# HDMI_OUTPUT_AD9889.net
KiCad netlist of a schematic drawn in Altium Designer
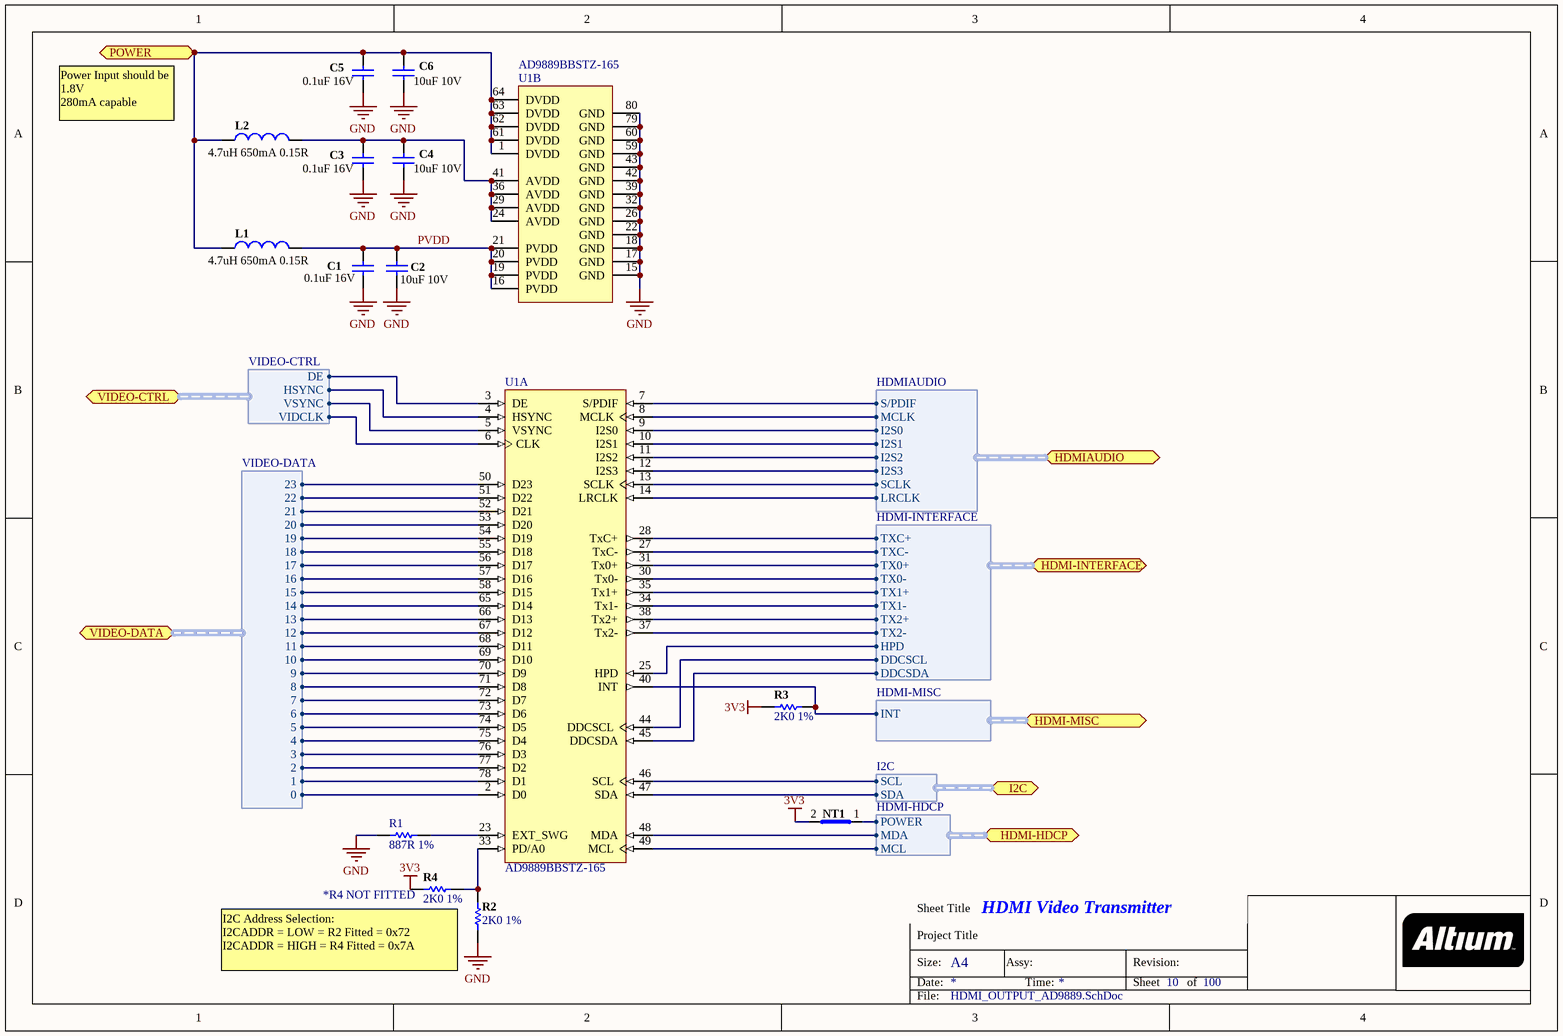
[diagram p0: HDMI_OUTPUT_AD9889.SchDoc]

(export (version "E")
  (design (tool "Eeschema 10.0.6"))
  (components
    (comp (ref "C1")
      (value "0.1uF 16V")
      (footprint "CAPC1005-STAR")
      (description "Capacitor, Ceramic, 0.1uF 10% 16V 0402 (1005) X7R")
      (fields (field (name "TOLERANCE") "10 %"))
      (libsource (lib "AltiumDesignLibrary") (part "CAP-NP"))
    )
    (comp (ref "C2")
      (value "10uF 10V")
      (footprint "CAPC2012-STAR")
      (description "Capacitor, Ceramic, 10uF 10% 10V 0805 (2012) X5R")
      (fields (field (name "TOLERANCE") "10 %"))
      (libsource (lib "AltiumDesignLibrary") (part "CAP-NP"))
    )
    (comp (ref "C3")
      (value "0.1uF 16V")
      (footprint "CAPC1005-STAR")
      (description "Capacitor, Ceramic, 0.1uF 10% 16V 0402 (1005) X7R")
      (fields (field (name "TOLERANCE") "10 %"))
      (libsource (lib "AltiumDesignLibrary") (part "CAP-NP"))
    )
    (comp (ref "C4")
      (value "10uF 10V")
      (footprint "CAPC2012-STAR")
      (description "Capacitor, Ceramic, 10uF 10% 10V 0805 (2012) X5R")
      (fields (field (name "TOLERANCE") "10 %"))
      (libsource (lib "AltiumDesignLibrary") (part "CAP-NP"))
    )
    (comp (ref "C5")
      (value "0.1uF 16V")
      (footprint "CAPC1005-STAR")
      (description "Capacitor, Ceramic, 0.1uF 10% 16V 0402 (1005) X7R")
      (fields (field (name "TOLERANCE") "10 %"))
      (libsource (lib "AltiumDesignLibrary") (part "CAP-NP"))
    )
    (comp (ref "C6")
      (value "10uF 10V")
      (footprint "CAPC2012-STAR")
      (description "Capacitor, Ceramic, 10uF 10% 10V 0805 (2012) X5R")
      (fields (field (name "TOLERANCE") "10 %"))
      (libsource (lib "AltiumDesignLibrary") (part "CAP-NP"))
    )
    (comp (ref "L1")
      (value "4.7uH 650mA 0.15R")
      (footprint "INDC3225")
      (description "Inductor, 4.7uH 650mA 0.15R 1210 (3225) LQH32CN4R7M11L")
      (libsource (lib "AltiumDesignLibrary") (part "IND"))
    )
    (comp (ref "L2")
      (value "4.7uH 650mA 0.15R")
      (footprint "INDC3225")
      (description "Inductor, 4.7uH 650mA 0.15R 1210 (3225) LQH32CN4R7M11L")
      (libsource (lib "AltiumDesignLibrary") (part "IND"))
    )
    (comp (ref "NT1")
      (value "Net Tie SMT2")
      (footprint "NETTIE-SMT2-31X39")
      (description "Net-Tie, Surface Mount, 2 x 2.0mm x 0.8mm SMT Pads - For 0.8mm Track")
      (libsource (lib "AltiumDesignLibrary") (part "NETTIE-SMT2"))
    )
    (comp (ref "R1")
      (value "887R 1%")
      (footprint "RESC1005-STAR")
      (description "Resistor, 887R 1% 0402 (1005)")
      (fields (field (name "TOLERANCE") "1 %"))
      (libsource (lib "AltiumDesignLibrary") (part "RES"))
    )
    (comp (ref "R2")
      (value "2K0 1%")
      (footprint "RESC1005-STAR")
      (description "Resistor, 2K0 1% 0402 (1005)")
      (fields (field (name "TOLERANCE") "1 %"))
      (libsource (lib "AltiumDesignLibrary") (part "RES"))
    )
    (comp (ref "R3")
      (value "2K0 1%")
      (footprint "RESC1005-STAR")
      (description "Resistor, 2K0 1% 0402 (1005)")
      (fields (field (name "TOLERANCE") "1 %"))
      (libsource (lib "AltiumDesignLibrary") (part "RES"))
    )
    (comp (ref "R4")
      (value "2K0 1%")
      (footprint "RESC1005-STAR")
      (description "Resistor, 2K0 1% 0402 (1005)")
      (fields (field (name "TOLERANCE") "1 %"))
      (libsource (lib "AltiumDesignLibrary") (part "RES"))
    )
    (comp (ref "U1")
      (value "AD9889BBSTZ-165")
      (footprint "ST-80-2_V")
      (description "AD9889, HDMI Video Transmitter, TQFP")
      (libsource (lib "AltiumDesignLibrary") (part "AD9889BBSTZ-165"))
    )
  )
  (nets
    (net (code "8") (name "/0") (class "Default")
      (node (ref "U1") (pin "2") (pinfunction "D0_2") (pintype "input"))
    )
    (net (code "9") (name "/1") (class "Default")
      (node (ref "U1") (pin "78") (pinfunction "D1_78") (pintype "input"))
    )
    (net (code "10") (name "/2") (class "Default")
      (node (ref "U1") (pin "77") (pinfunction "D2_77") (pintype "input"))
    )
    (net (code "11") (name "/3") (class "Default")
      (node (ref "U1") (pin "76") (pinfunction "D3_76") (pintype "input"))
    )
    (net (code "12") (name "/4") (class "Default")
      (node (ref "U1") (pin "75") (pinfunction "D4_75") (pintype "input"))
    )
    (net (code "13") (name "/5") (class "Default")
      (node (ref "U1") (pin "74") (pinfunction "D5_74") (pintype "input"))
    )
    (net (code "14") (name "/6") (class "Default")
      (node (ref "U1") (pin "73") (pinfunction "D6_73") (pintype "input"))
    )
    (net (code "15") (name "/7") (class "Default")
      (node (ref "U1") (pin "72") (pinfunction "D7_72") (pintype "input"))
    )
    (net (code "16") (name "/8") (class "Default")
      (node (ref "U1") (pin "71") (pinfunction "D8_71") (pintype "input"))
    )
    (net (code "17") (name "/9") (class "Default")
      (node (ref "U1") (pin "70") (pinfunction "D9_70") (pintype "input"))
    )
    (net (code "18") (name "/10") (class "Default")
      (node (ref "U1") (pin "69") (pinfunction "D10_69") (pintype "input"))
    )
    (net (code "19") (name "/11") (class "Default")
      (node (ref "U1") (pin "68") (pinfunction "D11_68") (pintype "input"))
    )
    (net (code "20") (name "/12") (class "Default")
      (node (ref "U1") (pin "67") (pinfunction "D12_67") (pintype "input"))
    )
    (net (code "21") (name "/13") (class "Default")
      (node (ref "U1") (pin "66") (pinfunction "D13_66") (pintype "input"))
    )
    (net (code "22") (name "/14") (class "Default")
      (node (ref "U1") (pin "65") (pinfunction "D14_65") (pintype "input"))
    )
    (net (code "23") (name "/15") (class "Default")
      (node (ref "U1") (pin "58") (pinfunction "D15_58") (pintype "input"))
    )
    (net (code "24") (name "/16") (class "Default")
      (node (ref "U1") (pin "57") (pinfunction "D16_57") (pintype "input"))
    )
    (net (code "25") (name "/17") (class "Default")
      (node (ref "U1") (pin "56") (pinfunction "D17_56") (pintype "input"))
    )
    (net (code "26") (name "/18") (class "Default")
      (node (ref "U1") (pin "55") (pinfunction "D18_55") (pintype "input"))
    )
    (net (code "27") (name "/19") (class "Default")
      (node (ref "U1") (pin "54") (pinfunction "D19_54") (pintype "input"))
    )
    (net (code "28") (name "/20") (class "Default")
      (node (ref "U1") (pin "53") (pinfunction "D20_53") (pintype "input"))
    )
    (net (code "29") (name "/21") (class "Default")
      (node (ref "U1") (pin "52") (pinfunction "D21_52") (pintype "input"))
    )
    (net (code "30") (name "/22") (class "Default")
      (node (ref "U1") (pin "51") (pinfunction "D22_51") (pintype "input"))
    )
    (net (code "31") (name "/23") (class "Default")
      (node (ref "U1") (pin "50") (pinfunction "D23_50") (pintype "input"))
    )
    (net (code "32") (name "/DDCSCL") (class "Default")
      (node (ref "U1") (pin "44") (pinfunction "DDCSCL_44") (pintype "input"))
    )
    (net (code "33") (name "/DDCSDA") (class "Default")
      (node (ref "U1") (pin "45") (pinfunction "DDCSDA_45") (pintype "input"))
    )
    (net (code "34") (name "/DE") (class "Default")
      (node (ref "U1") (pin "3") (pinfunction "DE_3") (pintype "input"))
    )
    (net (code "35") (name "/HPD") (class "Default")
      (node (ref "U1") (pin "25") (pinfunction "HPD_25") (pintype "input"))
    )
    (net (code "36") (name "/HSYNC") (class "Default")
      (node (ref "U1") (pin "4") (pinfunction "HSYNC_4") (pintype "input"))
    )
    (net (code "37") (name "/I2S0") (class "Default")
      (node (ref "U1") (pin "9") (pinfunction "I2S0_9") (pintype "input"))
    )
    (net (code "38") (name "/I2S1") (class "Default")
      (node (ref "U1") (pin "10") (pinfunction "I2S1_10") (pintype "input"))
    )
    (net (code "39") (name "/I2S2") (class "Default")
      (node (ref "U1") (pin "11") (pinfunction "I2S2_11") (pintype "input"))
    )
    (net (code "40") (name "/I2S3") (class "Default")
      (node (ref "U1") (pin "12") (pinfunction "I2S3_12") (pintype "input"))
    )
    (net (code "41") (name "/INT") (class "Default")
      (node (ref "R3") (pin "2") (pinfunction "2_2") (pintype "passive"))
      (node (ref "U1") (pin "40") (pinfunction "INT_40") (pintype "output"))
    )
    (net (code "42") (name "/LRCLK") (class "Default")
      (node (ref "U1") (pin "14") (pinfunction "LRCLK_14") (pintype "input"))
    )
    (net (code "43") (name "/MCL") (class "Default")
      (node (ref "U1") (pin "49") (pinfunction "MCL_49") (pintype "input"))
    )
    (net (code "44") (name "/MCLK") (class "Default")
      (node (ref "U1") (pin "8") (pinfunction "MCLK_8") (pintype "input"))
    )
    (net (code "45") (name "/MDA") (class "Default")
      (node (ref "U1") (pin "48") (pinfunction "MDA_48") (pintype "input"))
    )
    (net (code "46") (name "/POWER") (class "Default")
      (node (ref "C5") (pin "1") (pinfunction "1_1") (pintype "passive"))
      (node (ref "C6") (pin "1") (pinfunction "1_1") (pintype "passive"))
      (node (ref "L1") (pin "1") (pinfunction "1_1") (pintype "passive"))
      (node (ref "L2") (pin "1") (pinfunction "1_1") (pintype "passive"))
      (node (ref "U1") (pin "1") (pinfunction "DVDD_1") (pintype "power_in"))
      (node (ref "U1") (pin "61") (pinfunction "DVDD_61") (pintype "power_in"))
      (node (ref "U1") (pin "62") (pinfunction "DVDD_62") (pintype "power_in"))
      (node (ref "U1") (pin "63") (pinfunction "DVDD_63") (pintype "power_in"))
      (node (ref "U1") (pin "64") (pinfunction "DVDD_64") (pintype "power_in"))
    )
    (net (code "47") (name "/PVDD") (class "Default")
      (node (ref "C1") (pin "1") (pinfunction "1_1") (pintype "passive"))
      (node (ref "C2") (pin "1") (pinfunction "1_1") (pintype "passive"))
      (node (ref "L1") (pin "2") (pinfunction "2_2") (pintype "passive"))
      (node (ref "U1") (pin "16") (pinfunction "PVDD_16") (pintype "power_in"))
      (node (ref "U1") (pin "19") (pinfunction "PVDD_19") (pintype "power_in"))
      (node (ref "U1") (pin "20") (pinfunction "PVDD_20") (pintype "power_in"))
      (node (ref "U1") (pin "21") (pinfunction "PVDD_21") (pintype "power_in"))
    )
    (net (code "48") (name "/SCL") (class "Default")
      (node (ref "U1") (pin "46") (pinfunction "SCL_46") (pintype "input"))
    )
    (net (code "49") (name "/SCLK") (class "Default")
      (node (ref "U1") (pin "13") (pinfunction "SCLK_13") (pintype "input"))
    )
    (net (code "50") (name "/SDA") (class "Default")
      (node (ref "U1") (pin "47") (pinfunction "SDA_47") (pintype "input"))
    )
    (net (code "51") (name "/S{slash}PDIF") (class "Default")
      (node (ref "U1") (pin "7") (pinfunction "S/PDIF_7") (pintype "input"))
    )
    (net (code "52") (name "/TX0+") (class "Default")
      (node (ref "U1") (pin "31") (pinfunction "Tx0+_31") (pintype "output"))
    )
    (net (code "53") (name "/TX0-") (class "Default")
      (node (ref "U1") (pin "30") (pinfunction "Tx0-_30") (pintype "output"))
    )
    (net (code "54") (name "/TX1+") (class "Default")
      (node (ref "U1") (pin "35") (pinfunction "Tx1+_35") (pintype "output"))
    )
    (net (code "55") (name "/TX1-") (class "Default")
      (node (ref "U1") (pin "34") (pinfunction "Tx1-_34") (pintype "output"))
    )
    (net (code "56") (name "/TX2+") (class "Default")
      (node (ref "U1") (pin "38") (pinfunction "Tx2+_38") (pintype "output"))
    )
    (net (code "57") (name "/TX2-") (class "Default")
      (node (ref "U1") (pin "37") (pinfunction "Tx2-_37") (pintype "output"))
    )
    (net (code "58") (name "/TXC+") (class "Default")
      (node (ref "U1") (pin "28") (pinfunction "TxC+_28") (pintype "output"))
    )
    (net (code "59") (name "/TXC-") (class "Default")
      (node (ref "U1") (pin "27") (pinfunction "TxC-_27") (pintype "output"))
    )
    (net (code "60") (name "/VIDCLK") (class "Default")
      (node (ref "U1") (pin "6") (pinfunction "CLK_6") (pintype "input"))
    )
    (net (code "61") (name "/VSYNC") (class "Default")
      (node (ref "U1") (pin "5") (pinfunction "VSYNC_5") (pintype "input"))
    )
    (net (code "69") (name "3V3") (class "Default")
      (node (ref "NT1") (pin "2") (pinfunction "Net2_2") (pintype "passive"))
      (node (ref "R3") (pin "1") (pinfunction "1_1") (pintype "passive"))
      (node (ref "R4") (pin "1") (pinfunction "1_1") (pintype "passive"))
    )
    (net (code "70") (name "GND") (class "Default")
      (node (ref "C1") (pin "2") (pinfunction "2_2") (pintype "passive"))
      (node (ref "C2") (pin "2") (pinfunction "2_2") (pintype "passive"))
      (node (ref "C3") (pin "2") (pinfunction "2_2") (pintype "passive"))
      (node (ref "C4") (pin "2") (pinfunction "2_2") (pintype "passive"))
      (node (ref "C5") (pin "2") (pinfunction "2_2") (pintype "passive"))
      (node (ref "C6") (pin "2") (pinfunction "2_2") (pintype "passive"))
      (node (ref "R1") (pin "1") (pinfunction "1_1") (pintype "passive"))
      (node (ref "R2") (pin "2") (pinfunction "2_2") (pintype "passive"))
      (node (ref "U1") (pin "15") (pinfunction "GND_15") (pintype "power_in"))
      (node (ref "U1") (pin "17") (pinfunction "GND_17") (pintype "power_in"))
      (node (ref "U1") (pin "18") (pinfunction "GND_18") (pintype "power_in"))
      (node (ref "U1") (pin "22") (pinfunction "GND_22") (pintype "power_in"))
      (node (ref "U1") (pin "26") (pinfunction "GND_26") (pintype "power_in"))
      (node (ref "U1") (pin "32") (pinfunction "GND_32") (pintype "power_in"))
      (node (ref "U1") (pin "39") (pinfunction "GND_39") (pintype "power_in"))
      (node (ref "U1") (pin "42") (pinfunction "GND_42") (pintype "power_in"))
      (node (ref "U1") (pin "43") (pinfunction "GND_43") (pintype "power_in"))
      (node (ref "U1") (pin "59") (pinfunction "GND_59") (pintype "power_in"))
      (node (ref "U1") (pin "60") (pinfunction "GND_60") (pintype "power_in"))
      (node (ref "U1") (pin "79") (pinfunction "GND_79") (pintype "power_in"))
      (node (ref "U1") (pin "80") (pinfunction "GND_80") (pintype "power_in"))
    )
    (net (code "71") (name "Net-(C3-Pad1)") (class "Default")
      (node (ref "C3") (pin "1") (pinfunction "1_1") (pintype "passive"))
      (node (ref "C4") (pin "1") (pinfunction "1_1") (pintype "passive"))
      (node (ref "L2") (pin "2") (pinfunction "2_2") (pintype "passive"))
      (node (ref "U1") (pin "24") (pinfunction "AVDD_24") (pintype "power_in"))
      (node (ref "U1") (pin "29") (pinfunction "AVDD_29") (pintype "power_in"))
      (node (ref "U1") (pin "36") (pinfunction "AVDD_36") (pintype "power_in"))
      (node (ref "U1") (pin "41") (pinfunction "AVDD_41") (pintype "power_in"))
    )
    (net (code "72") (name "Net-(U1A-EXT_SWG)") (class "Default")
      (node (ref "R1") (pin "2") (pinfunction "2_2") (pintype "passive"))
      (node (ref "U1") (pin "23") (pinfunction "EXT_SWG_23") (pintype "input"))
    )
    (net (code "73") (name "Net-(U1A-PD{slash}A0)") (class "Default")
      (node (ref "R2") (pin "1") (pinfunction "1_1") (pintype "passive"))
      (node (ref "R4") (pin "2") (pinfunction "2_2") (pintype "passive"))
      (node (ref "U1") (pin "33") (pinfunction "PD/A0_33") (pintype "input"))
    )
    (net (code "74") (name "unconnected-(NT1-Net1-Pad1)") (class "Default")
      (node (ref "NT1") (pin "1") (pinfunction "Net1_1") (pintype "passive"))
    )
  )
)
